# rev02_9.net
KiCad netlist of a schematic drawn in Altium Designer
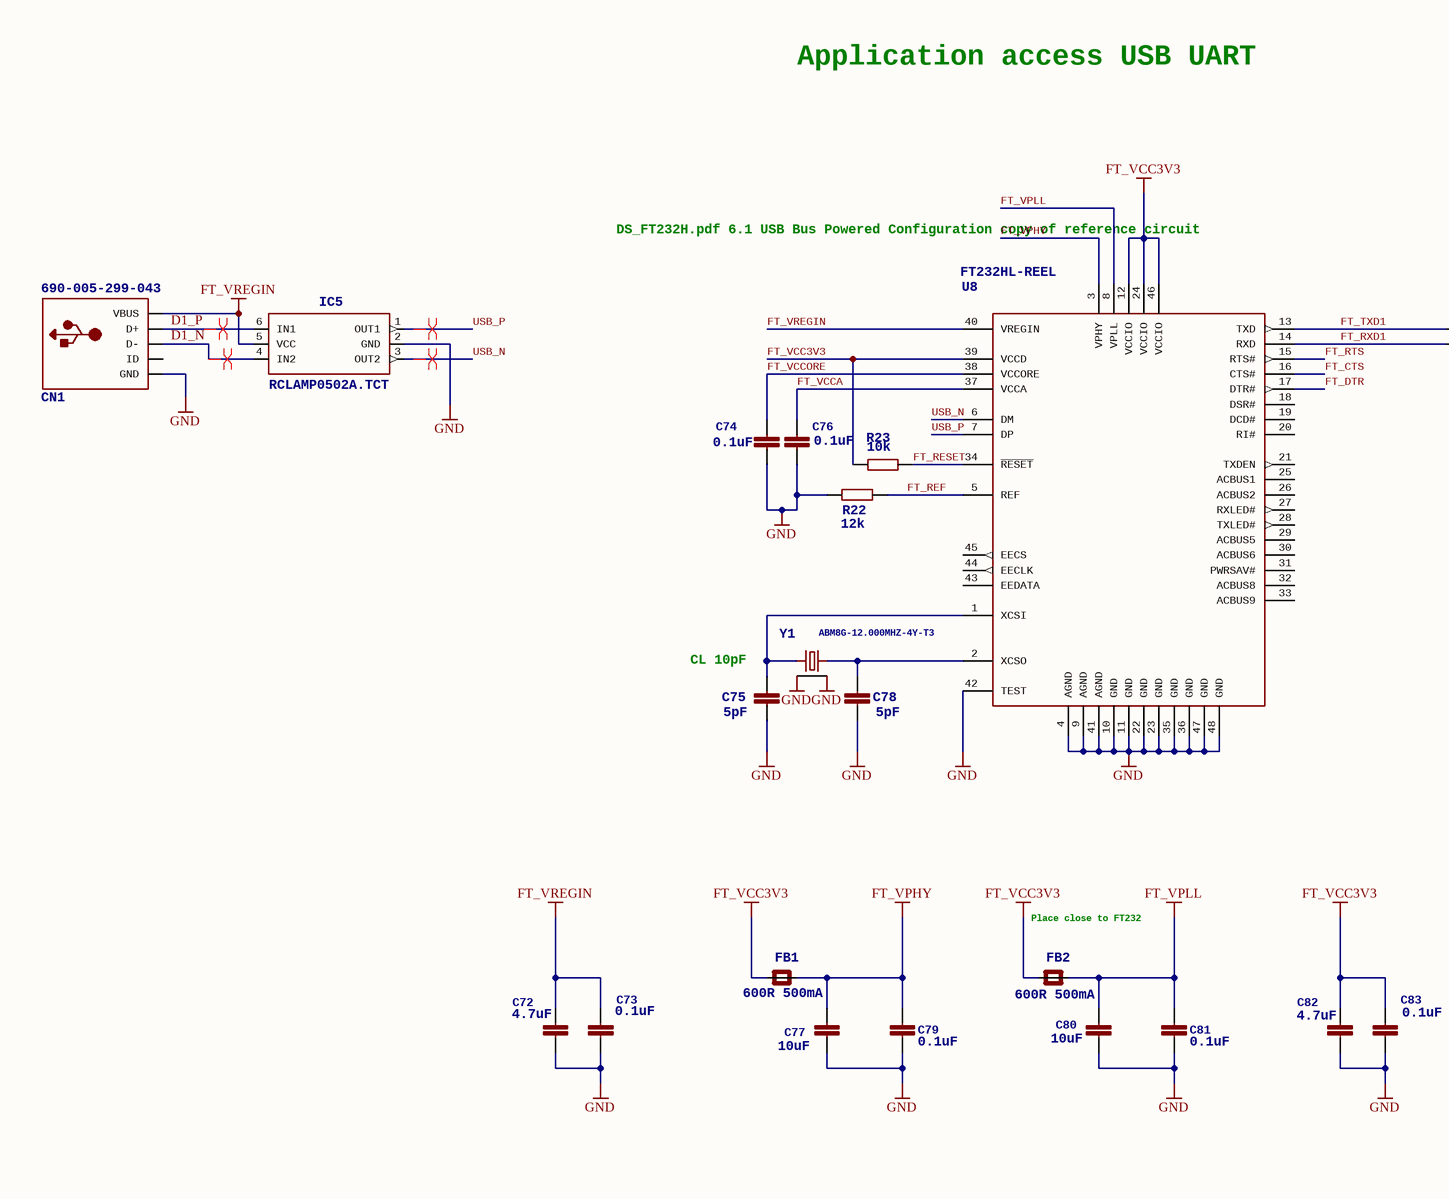
[diagram p0: rev02_9.SchDoc, left]
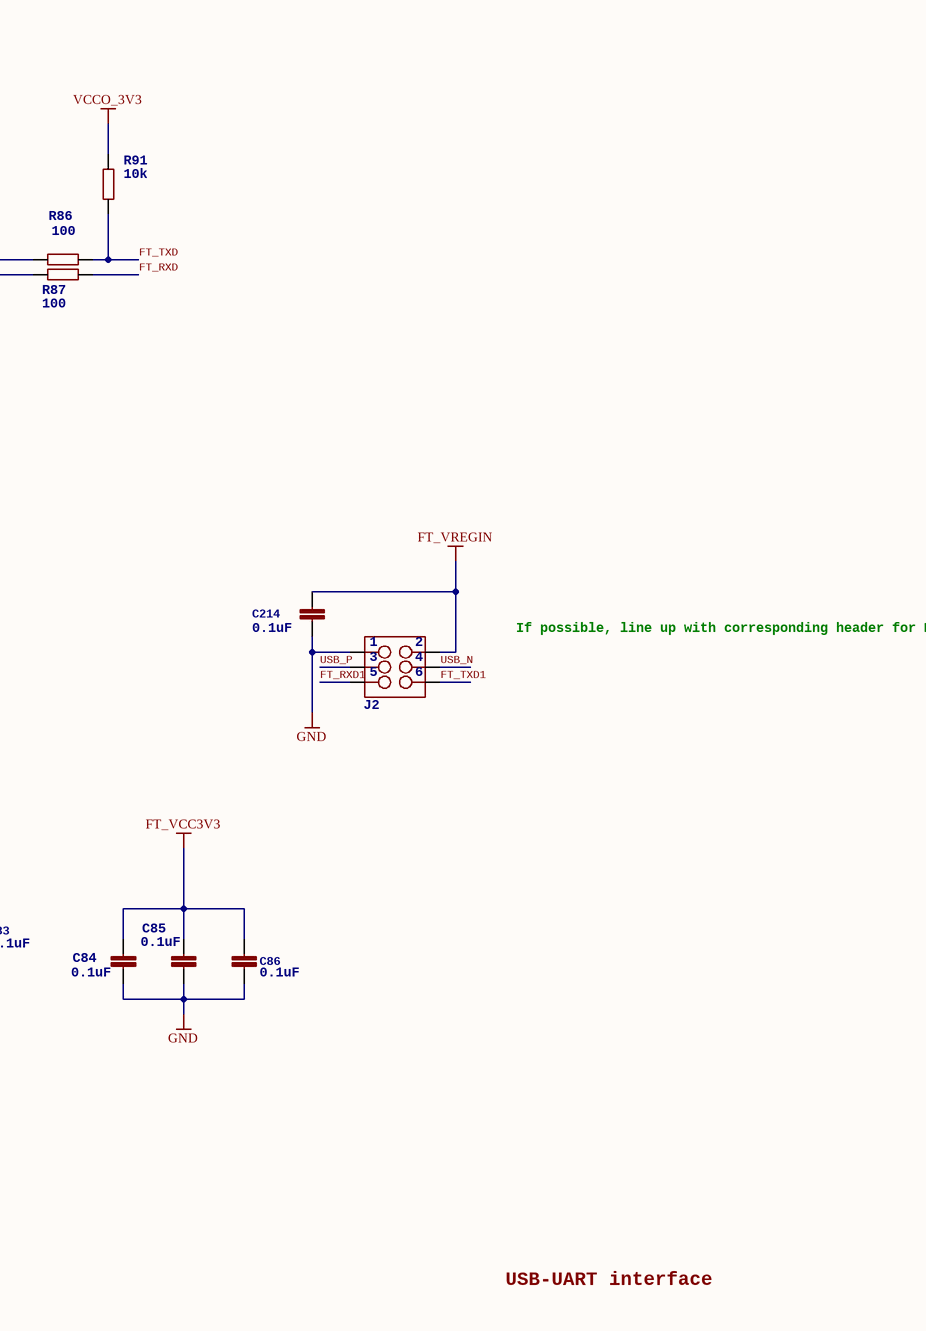
[diagram p1: rev02_9.SchDoc, right]

(export (version "E")
  (design (tool "Eeschema 10.0.6"))
  (components
    (comp (ref "C72")
      (value "4.7uF")
      (footprint "C_0805")
      (description "0805 CAPACITOR")
      (fields (field (name "Comment") "GRM21BR71A475KA73L"))
      (libsource (lib "resistor") (part "C-EUC0603"))
    )
    (comp (ref "C73")
      (value "0.1uF")
      (footprint "C_0402")
      (description "0402 CAPACITOR")
      (libsource (lib "resistor") (part "C-EUC0402"))
    )
    (comp (ref "C74")
      (value "0.1uF")
      (footprint "C_0402")
      (description "0402 CAPACITOR")
      (libsource (lib "resistor") (part "C-EUC0402"))
    )
    (comp (ref "C75")
      (value "5pF")
      (footprint "C_0402")
      (description "0402 CAPACITOR")
      (libsource (lib "") (part "C-EUC0402_1"))
    )
    (comp (ref "C76")
      (value "0.1uF")
      (footprint "C_0402")
      (description "0402 CAPACITOR")
      (libsource (lib "resistor") (part "C-EUC0402"))
    )
    (comp (ref "C77")
      (value "10uF")
      (footprint "C_0805")
      (description "0805 CAPACITOR")
      (libsource (lib "resistor") (part "C-EUC0805"))
    )
    (comp (ref "C78")
      (value "5pF")
      (footprint "C_0402")
      (description "0402 CAPACITOR")
      (libsource (lib "") (part "C-EUC0402_1"))
    )
    (comp (ref "C79")
      (value "0.1uF")
      (footprint "C_0402")
      (description "0402 CAPACITOR")
      (libsource (lib "resistor") (part "C-EUC0402"))
    )
    (comp (ref "C80")
      (value "10uF")
      (footprint "C_0805")
      (description "0805 CAPACITOR")
      (libsource (lib "resistor") (part "C-EUC0805"))
    )
    (comp (ref "C81")
      (value "0.1uF")
      (footprint "C_0402")
      (description "0402 CAPACITOR")
      (libsource (lib "resistor") (part "C-EUC0402"))
    )
    (comp (ref "C82")
      (value "4.7uF")
      (footprint "C_0805")
      (description "0805 CAPACITOR")
      (fields (field (name "Comment") "GRM21BR71A475KA73L"))
      (libsource (lib "resistor") (part "C-EUC0603"))
    )
    (comp (ref "C83")
      (value "0.1uF")
      (footprint "C_0402")
      (description "0402 CAPACITOR")
      (libsource (lib "resistor") (part "C-EUC0402"))
    )
    (comp (ref "C84")
      (value "0.1uF")
      (footprint "C_0402")
      (description "0402 CAPACITOR")
      (libsource (lib "resistor") (part "C-EUC0402"))
    )
    (comp (ref "C85")
      (value "0.1uF")
      (footprint "C_0402")
      (description "0402 CAPACITOR")
      (libsource (lib "resistor") (part "C-EUC0402"))
    )
    (comp (ref "C86")
      (value "0.1uF")
      (footprint "C_0402")
      (description "0402 CAPACITOR")
      (libsource (lib "resistor") (part "C-EUC0402"))
    )
    (comp (ref "C214")
      (value "0.1uF")
      (footprint "C_0402")
      (description "0402 CAPACITOR")
      (libsource (lib "resistor") (part "C-EUC0402"))
    )
    (comp (ref "CN1")
      (value "690-005-299-043")
      (footprint "USB-MINIB")
      (description "mini USB type B Connector")
      (libsource (lib "adafruit") (part "USBMINIB"))
    )
    (comp (ref "FB1")
      (value "FBMH1608HL601-T")
      (footprint "L_0603")
      (description "Ferrite Bead 600 Ohm 500mA")
      (fields (field (name ">NAME") "FB1") (field (name ">VALUE") "600R 500mA"))
      (libsource (lib "microbuilder") (part "FERRITE_0603MP"))
    )
    (comp (ref "FB2")
      (value "FBMH1608HL601-T")
      (footprint "L_0603")
      (description "Ferrite Bead 600 Ohm 500mA")
      (fields (field (name ">NAME") "FB2") (field (name ">VALUE") "600R 500mA"))
      (libsource (lib "microbuilder") (part "FERRITE_0603MP"))
    )
    (comp (ref "IC5")
      (value "RCLAMP0502A.TCT")
      (footprint "RCLAMP0502A")
      (description "USB protective diodes")
      (fields (field (name "MFR") "SEMTECH") (field (name "MPN") "RCLAMP0502A") (field (name ">NAME") "IC5"))
      (libsource (lib "UsedComponents") (part "RCLAMP0502ASC-89"))
    )
    (comp (ref "J2")
      (value "M03X2NO_SILK")
      (footprint "PLD-6")
      (description "2x3 .1\" header")
      (fields
        (field (name "1") "1")
        (field (name "2") "2")
        (field (name "3") "3")
        (field (name "4") "4")
        (field (name "5") "5")
        (field (name "6") "6")
      )
      (libsource (lib "SparkFun-Connectors") (part "M03X2NO_SILK"))
    )
    (comp (ref "R22")
      (value "12k")
      (footprint "R_0402")
      (description "0402 Resistor 1%")
      (libsource (lib "resistor") (part "R-EU_R0402"))
    )
    (comp (ref "R23")
      (value "10k")
      (footprint "R_0402")
      (description "0402 Resistor 5%")
      (fields (field (name "TOLERANCE") "5%") (field (name ">NAME") "R23"))
      (libsource (lib "resistor") (part "R-EU_R0402"))
    )
    (comp (ref "R86")
      (value "100")
      (footprint "R_0402")
      (description "0402 Resistor 5%")
      (libsource (lib "resistor") (part "R-EU_R0402"))
    )
    (comp (ref "R87")
      (value "100")
      (footprint "R_0402")
      (description "0402 Resistor 5%")
      (libsource (lib "resistor") (part "R-EU_R0402"))
    )
    (comp (ref "R91")
      (value "10k")
      (footprint "R_0402")
      (description "0402 Resistor 5%")
      (libsource (lib "resistor") (part "R-EU_R0402"))
    )
    (comp (ref "U8")
      (value "FT232HL-REEL")
      (footprint "LQFP-48")
      (description "INTERFACE, USB - UART/FIFO")
      (fields (field (name ">NAME") "U8"))
      (libsource (lib "Alpha-IC") (part "FT232H_SERIAL"))
    )
    (comp (ref "Y1")
      (value "ABM8G-12.000MHZ-4Y-T3")
      (footprint "CRYSTAL_3.2X2.5")
      (description "Crystal 12MHz")
      (libsource (lib "rev02_1") (part "CRYSTALTHIN"))
    )
  )
  (nets
    (net (code "1") (name "/D1_N") (class "Default")
      (node (ref "CN1") (pin "D-") (pinfunction "D-_D-") (pintype "passive"))
      (node (ref "IC5") (pin "4") (pinfunction "IN2_4") (pintype "passive"))
    )
    (net (code "2") (name "/D1_P") (class "Default")
      (node (ref "CN1") (pin "D+") (pinfunction "D+_D+") (pintype "passive"))
      (node (ref "IC5") (pin "6") (pinfunction "IN1_6") (pintype "passive"))
    )
    (net (code "3") (name "/FT_CTS") (class "Default")
      (node (ref "U8") (pin "16") (pinfunction "CTS#_16") (pintype "passive"))
    )
    (net (code "4") (name "/FT_DTR") (class "Default")
      (node (ref "U8") (pin "17") (pinfunction "DTR#_17") (pintype "output"))
    )
    (net (code "5") (name "/FT_REF") (class "Default")
      (node (ref "R22") (pin "1") (pinfunction "1_1") (pintype "passive"))
      (node (ref "U8") (pin "5") (pinfunction "REF_5") (pintype "passive"))
    )
    (net (code "6") (name "/FT_RESET") (class "Default")
      (node (ref "R23") (pin "1") (pinfunction "1_1") (pintype "passive"))
      (node (ref "U8") (pin "34") (pinfunction "~{RESET}_34") (pintype "passive"))
    )
    (net (code "7") (name "/FT_RTS") (class "Default")
      (node (ref "U8") (pin "15") (pinfunction "RTS#_15") (pintype "output"))
    )
    (net (code "8") (name "/FT_RXD") (class "Default")
      (node (ref "R87") (pin "1") (pinfunction "1_1") (pintype "passive"))
    )
    (net (code "9") (name "/FT_RXD1") (class "Default")
      (node (ref "J2") (pin "5") (pinfunction "5_5") (pintype "passive"))
      (node (ref "R87") (pin "2") (pinfunction "2_2") (pintype "passive"))
      (node (ref "U8") (pin "14") (pinfunction "RXD_14") (pintype "passive"))
    )
    (net (code "10") (name "/FT_TXD") (class "Default")
      (node (ref "R86") (pin "1") (pinfunction "1_1") (pintype "passive"))
      (node (ref "R91") (pin "2") (pinfunction "2_2") (pintype "passive"))
    )
    (net (code "11") (name "/FT_TXD1") (class "Default")
      (node (ref "J2") (pin "6") (pinfunction "6_6") (pintype "passive"))
      (node (ref "R86") (pin "2") (pinfunction "2_2") (pintype "passive"))
      (node (ref "U8") (pin "13") (pinfunction "TXD_13") (pintype "output"))
    )
    (net (code "12") (name "/FT_VCCA") (class "Default")
      (node (ref "C76") (pin "1") (pinfunction "1_1") (pintype "passive"))
      (node (ref "U8") (pin "37") (pinfunction "VCCA_37") (pintype "power_in"))
    )
    (net (code "13") (name "/FT_VCCORE") (class "Default")
      (node (ref "C74") (pin "1") (pinfunction "1_1") (pintype "passive"))
      (node (ref "U8") (pin "38") (pinfunction "VCCORE_38") (pintype "power_in"))
    )
    (net (code "14") (name "/USB_N") (class "Default")
      (node (ref "IC5") (pin "3") (pinfunction "OUT2_3") (pintype "output"))
      (node (ref "J2") (pin "4") (pinfunction "4_4") (pintype "passive"))
      (node (ref "U8") (pin "6") (pinfunction "DM_6") (pintype "passive"))
    )
    (net (code "15") (name "/USB_P") (class "Default")
      (node (ref "IC5") (pin "1") (pinfunction "OUT1_1") (pintype "output"))
      (node (ref "J2") (pin "3") (pinfunction "3_3") (pintype "passive"))
      (node (ref "U8") (pin "7") (pinfunction "DP_7") (pintype "passive"))
    )
    (net (code "16") (name "FT_VCC3V3") (class "Default")
      (node (ref "C82") (pin "1") (pinfunction "1_1") (pintype "passive"))
      (node (ref "C83") (pin "1") (pinfunction "1_1") (pintype "passive"))
      (node (ref "C84") (pin "1") (pinfunction "1_1") (pintype "passive"))
      (node (ref "C85") (pin "1") (pinfunction "1_1") (pintype "passive"))
      (node (ref "C86") (pin "1") (pinfunction "1_1") (pintype "passive"))
      (node (ref "FB1") (pin "1") (pinfunction "P$1_1") (pintype "passive"))
      (node (ref "FB2") (pin "1") (pinfunction "P$1_1") (pintype "passive"))
      (node (ref "R23") (pin "2") (pinfunction "2_2") (pintype "passive"))
      (node (ref "U8") (pin "12") (pinfunction "VCCIO_12") (pintype "power_in"))
      (node (ref "U8") (pin "24") (pinfunction "VCCIO_24") (pintype "power_in"))
      (node (ref "U8") (pin "39") (pinfunction "VCCD_39") (pintype "power_in"))
      (node (ref "U8") (pin "46") (pinfunction "VCCIO_46") (pintype "power_in"))
    )
    (net (code "17") (name "FT_VPHY") (class "Default")
      (node (ref "C77") (pin "1") (pinfunction "1_1") (pintype "passive"))
      (node (ref "C79") (pin "1") (pinfunction "1_1") (pintype "passive"))
      (node (ref "FB1") (pin "2") (pinfunction "P$2_2") (pintype "passive"))
      (node (ref "U8") (pin "3") (pinfunction "VPHY_3") (pintype "passive"))
    )
    (net (code "18") (name "FT_VPLL") (class "Default")
      (node (ref "C80") (pin "1") (pinfunction "1_1") (pintype "passive"))
      (node (ref "C81") (pin "1") (pinfunction "1_1") (pintype "passive"))
      (node (ref "FB2") (pin "2") (pinfunction "P$2_2") (pintype "passive"))
      (node (ref "U8") (pin "8") (pinfunction "VPLL_8") (pintype "passive"))
    )
    (net (code "19") (name "FT_VREGIN") (class "Default")
      (node (ref "C214") (pin "1") (pinfunction "1_1") (pintype "passive"))
      (node (ref "C72") (pin "1") (pinfunction "1_1") (pintype "passive"))
      (node (ref "C73") (pin "1") (pinfunction "1_1") (pintype "passive"))
      (node (ref "CN1") (pin "VBUS") (pinfunction "VBUS_VBUS") (pintype "power_in"))
      (node (ref "IC5") (pin "5") (pinfunction "VCC_5") (pintype "power_in"))
      (node (ref "J2") (pin "2") (pinfunction "2_2") (pintype "passive"))
      (node (ref "U8") (pin "40") (pinfunction "VREGIN_40") (pintype "power_in"))
    )
    (net (code "20") (name "GND") (class "Default")
      (node (ref "C214") (pin "2") (pinfunction "2_2") (pintype "passive"))
      (node (ref "C72") (pin "2") (pinfunction "2_2") (pintype "passive"))
      (node (ref "C73") (pin "2") (pinfunction "2_2") (pintype "passive"))
      (node (ref "C74") (pin "2") (pinfunction "2_2") (pintype "passive"))
      (node (ref "C75") (pin "1") (pinfunction "1_1") (pintype "passive"))
      (node (ref "C76") (pin "2") (pinfunction "2_2") (pintype "passive"))
      (node (ref "C77") (pin "2") (pinfunction "2_2") (pintype "passive"))
      (node (ref "C78") (pin "1") (pinfunction "1_1") (pintype "passive"))
      (node (ref "C79") (pin "2") (pinfunction "2_2") (pintype "passive"))
      (node (ref "C80") (pin "2") (pinfunction "2_2") (pintype "passive"))
      (node (ref "C81") (pin "2") (pinfunction "2_2") (pintype "passive"))
      (node (ref "C82") (pin "2") (pinfunction "2_2") (pintype "passive"))
      (node (ref "C83") (pin "2") (pinfunction "2_2") (pintype "passive"))
      (node (ref "C84") (pin "2") (pinfunction "2_2") (pintype "passive"))
      (node (ref "C85") (pin "2") (pinfunction "2_2") (pintype "passive"))
      (node (ref "C86") (pin "2") (pinfunction "2_2") (pintype "passive"))
      (node (ref "CN1") (pin "GND") (pinfunction "GND_GND") (pintype "power_in"))
      (node (ref "IC5") (pin "2") (pinfunction "GND_2") (pintype "power_in"))
      (node (ref "J2") (pin "1") (pinfunction "1_1") (pintype "passive"))
      (node (ref "R22") (pin "2") (pinfunction "2_2") (pintype "passive"))
      (node (ref "U8") (pin "10") (pinfunction "GND_10") (pintype "power_in"))
      (node (ref "U8") (pin "11") (pinfunction "GND_11") (pintype "power_in"))
      (node (ref "U8") (pin "22") (pinfunction "GND_22") (pintype "power_in"))
      (node (ref "U8") (pin "23") (pinfunction "GND_23") (pintype "power_in"))
      (node (ref "U8") (pin "35") (pinfunction "GND_35") (pintype "power_in"))
      (node (ref "U8") (pin "36") (pinfunction "GND_36") (pintype "power_in"))
      (node (ref "U8") (pin "4") (pinfunction "AGND_4") (pintype "power_in"))
      (node (ref "U8") (pin "41") (pinfunction "AGND_41") (pintype "power_in"))
      (node (ref "U8") (pin "42") (pinfunction "TEST_42") (pintype "passive"))
      (node (ref "U8") (pin "47") (pinfunction "GND_47") (pintype "power_in"))
      (node (ref "U8") (pin "48") (pinfunction "GND_48") (pintype "power_in"))
      (node (ref "U8") (pin "9") (pinfunction "AGND_9") (pintype "power_in"))
      (node (ref "Y1") (pin "2") (pinfunction "2_2") (pintype "passive"))
      (node (ref "Y1") (pin "4") (pinfunction "4_4") (pintype "passive"))
    )
    (net (code "21") (name "Net-(U8-XCSI)") (class "Default")
      (node (ref "C75") (pin "2") (pinfunction "2_2") (pintype "passive"))
      (node (ref "U8") (pin "1") (pinfunction "XCSI_1") (pintype "passive"))
      (node (ref "Y1") (pin "3") (pinfunction "3_3") (pintype "passive"))
    )
    (net (code "22") (name "Net-(U8-XCSO)") (class "Default")
      (node (ref "C78") (pin "2") (pinfunction "2_2") (pintype "passive"))
      (node (ref "U8") (pin "2") (pinfunction "XCSO_2") (pintype "passive"))
      (node (ref "Y1") (pin "1") (pinfunction "1_1") (pintype "passive"))
    )
    (net (code "23") (name "VCCO_3V3") (class "Default")
      (node (ref "R91") (pin "1") (pinfunction "1_1") (pintype "passive"))
    )
    (net (code "24") (name "unconnected-(CN1-PadID)") (class "Default")
      (node (ref "CN1") (pin "ID") (pinfunction "ID_ID") (pintype "passive"))
    )
    (net (code "25") (name "unconnected-(U8-ACBUS1-Pad25)") (class "Default")
      (node (ref "U8") (pin "25") (pinfunction "ACBUS1_25") (pintype "passive"))
    )
    (net (code "26") (name "unconnected-(U8-ACBUS2-Pad26)") (class "Default")
      (node (ref "U8") (pin "26") (pinfunction "ACBUS2_26") (pintype "passive"))
    )
    (net (code "27") (name "unconnected-(U8-ACBUS5-Pad29)") (class "Default")
      (node (ref "U8") (pin "29") (pinfunction "ACBUS5_29") (pintype "passive"))
    )
    (net (code "28") (name "unconnected-(U8-ACBUS6-Pad30)") (class "Default")
      (node (ref "U8") (pin "30") (pinfunction "ACBUS6_30") (pintype "passive"))
    )
    (net (code "29") (name "unconnected-(U8-ACBUS8-Pad32)") (class "Default")
      (node (ref "U8") (pin "32") (pinfunction "ACBUS8_32") (pintype "passive"))
    )
    (net (code "30") (name "unconnected-(U8-ACBUS9-Pad33)") (class "Default")
      (node (ref "U8") (pin "33") (pinfunction "ACBUS9_33") (pintype "passive"))
    )
    (net (code "31") (name "unconnected-(U8-DCD#-Pad19)") (class "Default")
      (node (ref "U8") (pin "19") (pinfunction "DCD#_19") (pintype "passive"))
    )
    (net (code "32") (name "unconnected-(U8-DSR#-Pad18)") (class "Default")
      (node (ref "U8") (pin "18") (pinfunction "DSR#_18") (pintype "passive"))
    )
    (net (code "33") (name "unconnected-(U8-EECLK-Pad44)") (class "Default")
      (node (ref "U8") (pin "44") (pinfunction "EECLK_44") (pintype "output"))
    )
    (net (code "34") (name "unconnected-(U8-EECS-Pad45)") (class "Default")
      (node (ref "U8") (pin "45") (pinfunction "EECS_45") (pintype "output"))
    )
    (net (code "35") (name "unconnected-(U8-EEDATA-Pad43)") (class "Default")
      (node (ref "U8") (pin "43") (pinfunction "EEDATA_43") (pintype "passive"))
    )
    (net (code "36") (name "unconnected-(U8-PWRSAV#-Pad31)") (class "Default")
      (node (ref "U8") (pin "31") (pinfunction "PWRSAV#_31") (pintype "passive"))
    )
    (net (code "37") (name "unconnected-(U8-RI#-Pad20)") (class "Default")
      (node (ref "U8") (pin "20") (pinfunction "RI#_20") (pintype "passive"))
    )
    (net (code "38") (name "unconnected-(U8-RXLED#-Pad27)") (class "Default")
      (node (ref "U8") (pin "27") (pinfunction "RXLED#_27") (pintype "output"))
    )
    (net (code "39") (name "unconnected-(U8-TXDEN-Pad21)") (class "Default")
      (node (ref "U8") (pin "21") (pinfunction "TXDEN_21") (pintype "output"))
    )
    (net (code "40") (name "unconnected-(U8-TXLED#-Pad28)") (class "Default")
      (node (ref "U8") (pin "28") (pinfunction "TXLED#_28") (pintype "output"))
    )
  )
)
